# RF.net
KiCad netlist of a schematic drawn in Altium Designer
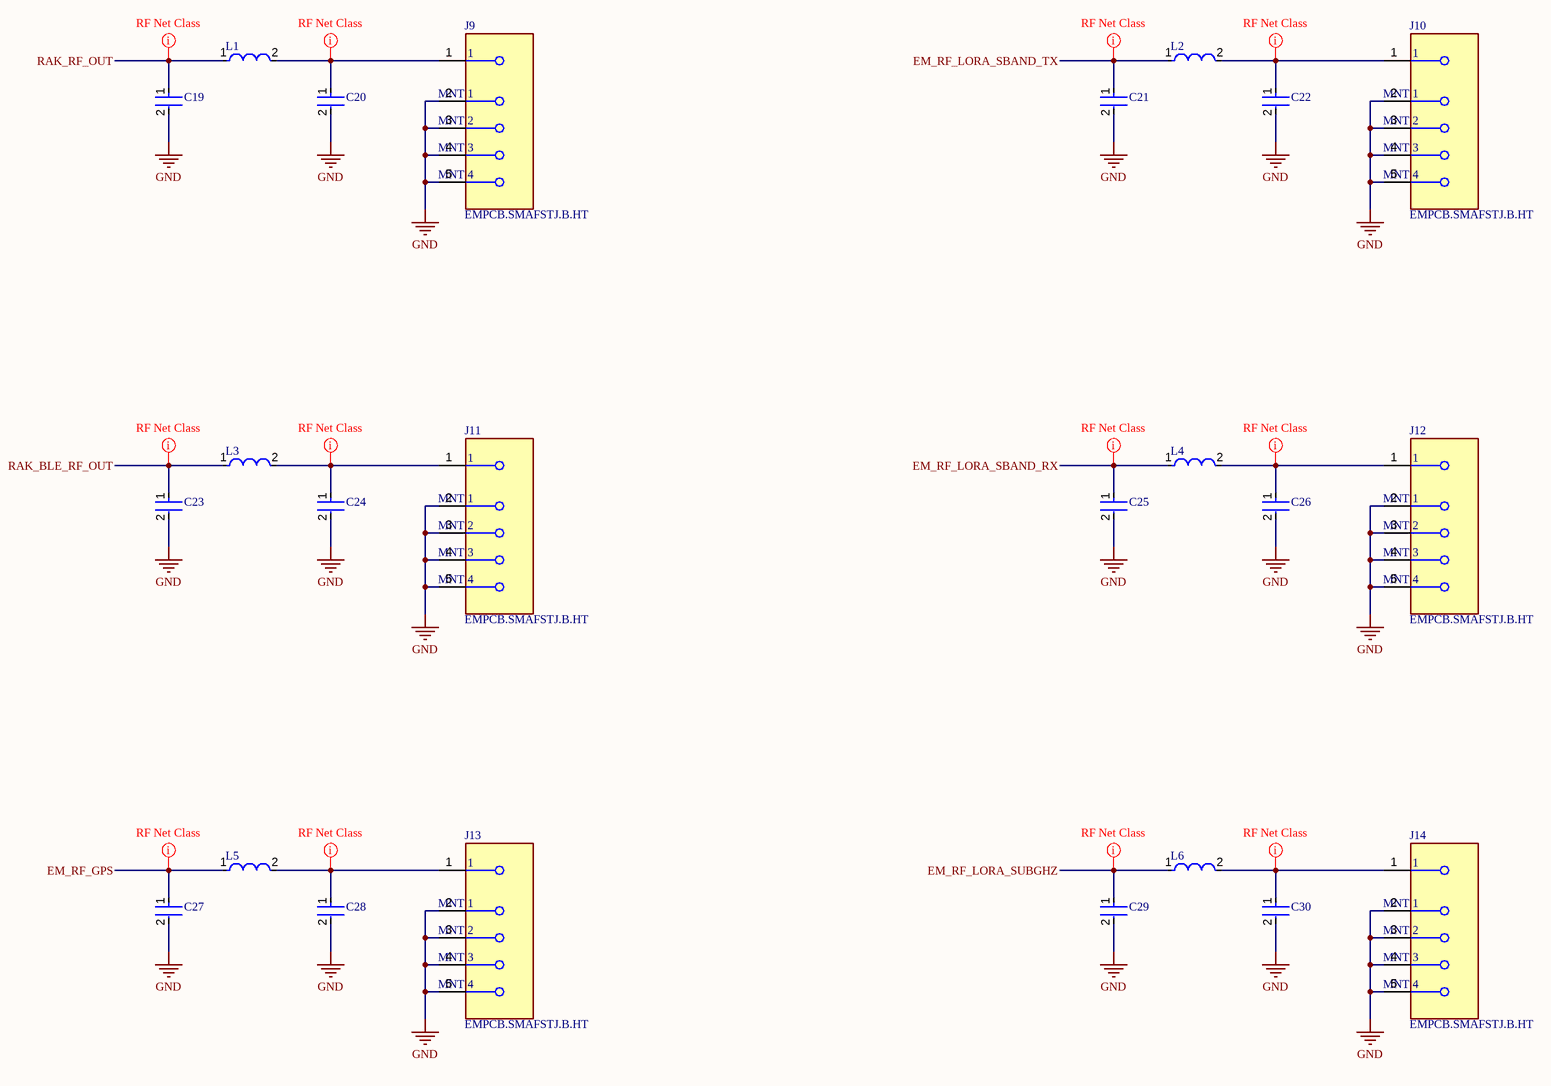
[diagram p0: RF.SchDoc]

(export (version "E")
  (design (tool "Eeschema 10.0.6"))
  (components
    (comp (ref "C19")
      (value "GJM1555C1H5R0CB01D")
      (footprint "FP-GJM155-0_05-MFG")
      (description "Multi-Layer Ceramic Capacitor 5pF C0G  ±0.25pF 0402 Paper T/R")
      (libsource (lib "ApolloEcho_Dev_Kit") (part "02cd4be3c70576c341d710602a673aa"))
    )
    (comp (ref "C20")
      (value "GJM1555C1H5R0CB01D")
      (footprint "FP-GJM155-0_05-MFG")
      (description "Multi-Layer Ceramic Capacitor 5pF C0G  ±0.25pF 0402 Paper T/R")
      (libsource (lib "ApolloEcho_Dev_Kit") (part "02cd4be3c70576c341d710602a673aa"))
    )
    (comp (ref "C21")
      (value "GJM1555C1H5R0CB01D")
      (footprint "FP-GJM155-0_05-MFG")
      (description "Multi-Layer Ceramic Capacitor 5pF C0G  ±0.25pF 0402 Paper T/R")
      (libsource (lib "ApolloEcho_Dev_Kit") (part "02cd4be3c70576c341d710602a673aa"))
    )
    (comp (ref "C22")
      (value "GJM1555C1H5R0CB01D")
      (footprint "FP-GJM155-0_05-MFG")
      (description "Multi-Layer Ceramic Capacitor 5pF C0G  ±0.25pF 0402 Paper T/R")
      (libsource (lib "ApolloEcho_Dev_Kit") (part "02cd4be3c70576c341d710602a673aa"))
    )
    (comp (ref "C23")
      (value "GJM1555C1H5R0CB01D")
      (footprint "FP-GJM155-0_05-MFG")
      (description "Multi-Layer Ceramic Capacitor 5pF C0G  ±0.25pF 0402 Paper T/R")
      (libsource (lib "ApolloEcho_Dev_Kit") (part "02cd4be3c70576c341d710602a673aa"))
    )
    (comp (ref "C24")
      (value "GJM1555C1H5R0CB01D")
      (footprint "FP-GJM155-0_05-MFG")
      (description "Multi-Layer Ceramic Capacitor 5pF C0G  ±0.25pF 0402 Paper T/R")
      (libsource (lib "ApolloEcho_Dev_Kit") (part "02cd4be3c70576c341d710602a673aa"))
    )
    (comp (ref "C25")
      (value "GJM1555C1H5R0CB01D")
      (footprint "FP-GJM155-0_05-MFG")
      (description "Multi-Layer Ceramic Capacitor 5pF C0G  ±0.25pF 0402 Paper T/R")
      (libsource (lib "ApolloEcho_Dev_Kit") (part "02cd4be3c70576c341d710602a673aa"))
    )
    (comp (ref "C26")
      (value "GJM1555C1H5R0CB01D")
      (footprint "FP-GJM155-0_05-MFG")
      (description "Multi-Layer Ceramic Capacitor 5pF C0G  ±0.25pF 0402 Paper T/R")
      (libsource (lib "ApolloEcho_Dev_Kit") (part "02cd4be3c70576c341d710602a673aa"))
    )
    (comp (ref "C27")
      (value "GJM1555C1H5R0CB01D")
      (footprint "FP-GJM155-0_05-MFG")
      (description "Multi-Layer Ceramic Capacitor 5pF C0G  ±0.25pF 0402 Paper T/R")
      (libsource (lib "ApolloEcho_Dev_Kit") (part "02cd4be3c70576c341d710602a673aa"))
    )
    (comp (ref "C28")
      (value "GJM1555C1H5R0CB01D")
      (footprint "FP-GJM155-0_05-MFG")
      (description "Multi-Layer Ceramic Capacitor 5pF C0G  ±0.25pF 0402 Paper T/R")
      (libsource (lib "ApolloEcho_Dev_Kit") (part "02cd4be3c70576c341d710602a673aa"))
    )
    (comp (ref "C29")
      (value "GJM1555C1H5R0CB01D")
      (footprint "FP-GJM155-0_05-MFG")
      (description "Multi-Layer Ceramic Capacitor 5pF C0G  ±0.25pF 0402 Paper T/R")
      (libsource (lib "ApolloEcho_Dev_Kit") (part "02cd4be3c70576c341d710602a673aa"))
    )
    (comp (ref "C30")
      (value "GJM1555C1H5R0CB01D")
      (footprint "FP-GJM155-0_05-MFG")
      (description "Multi-Layer Ceramic Capacitor 5pF C0G  ±0.25pF 0402 Paper T/R")
      (libsource (lib "ApolloEcho_Dev_Kit") (part "02cd4be3c70576c341d710602a673aa"))
    )
    (comp (ref "J9")
      (value "EMPCB.SMAFSTJ.B.HT")
      (footprint "FP-EMPCB_SMAFSTJ_B_HT-MFG")
      (description "CONN SMA JACK STR 50OHM EDGE MNT")
      (fields
        (field (name "OCTOPART") "https://octopart.com/empcb.smafstj.b.ht-taoglas-24204431")
        (field (name "MANUFACTURER") "Taoglas Limited")
      )
      (libsource (lib "ApolloEcho_Dev_Kit") (part "c65b8a639cdaef1819ea20b5466f8fa"))
    )
    (comp (ref "J10")
      (value "EMPCB.SMAFSTJ.B.HT")
      (footprint "FP-EMPCB_SMAFSTJ_B_HT-MFG")
      (description "CONN SMA JACK STR 50OHM EDGE MNT")
      (fields
        (field (name "OCTOPART") "https://octopart.com/empcb.smafstj.b.ht-taoglas-24204431")
        (field (name "MANUFACTURER") "Taoglas Limited")
      )
      (libsource (lib "ApolloEcho_Dev_Kit") (part "c65b8a639cdaef1819ea20b5466f8fa"))
    )
    (comp (ref "J11")
      (value "EMPCB.SMAFSTJ.B.HT")
      (footprint "FP-EMPCB_SMAFSTJ_B_HT-MFG")
      (description "CONN SMA JACK STR 50OHM EDGE MNT")
      (fields
        (field (name "OCTOPART") "https://octopart.com/empcb.smafstj.b.ht-taoglas-24204431")
        (field (name "MANUFACTURER") "Taoglas Limited")
      )
      (libsource (lib "ApolloEcho_Dev_Kit") (part "c65b8a639cdaef1819ea20b5466f8fa"))
    )
    (comp (ref "J12")
      (value "EMPCB.SMAFSTJ.B.HT")
      (footprint "FP-EMPCB_SMAFSTJ_B_HT-MFG")
      (description "CONN SMA JACK STR 50OHM EDGE MNT")
      (fields
        (field (name "OCTOPART") "https://octopart.com/empcb.smafstj.b.ht-taoglas-24204431")
        (field (name "MANUFACTURER") "Taoglas Limited")
      )
      (libsource (lib "ApolloEcho_Dev_Kit") (part "c65b8a639cdaef1819ea20b5466f8fa"))
    )
    (comp (ref "J13")
      (value "EMPCB.SMAFSTJ.B.HT")
      (footprint "FP-EMPCB_SMAFSTJ_B_HT-MFG")
      (description "CONN SMA JACK STR 50OHM EDGE MNT")
      (fields
        (field (name "OCTOPART") "https://octopart.com/empcb.smafstj.b.ht-taoglas-24204431")
        (field (name "MANUFACTURER") "Taoglas Limited")
      )
      (libsource (lib "ApolloEcho_Dev_Kit") (part "c65b8a639cdaef1819ea20b5466f8fa"))
    )
    (comp (ref "J14")
      (value "EMPCB.SMAFSTJ.B.HT")
      (footprint "FP-EMPCB_SMAFSTJ_B_HT-MFG")
      (description "CONN SMA JACK STR 50OHM EDGE MNT")
      (fields
        (field (name "OCTOPART") "https://octopart.com/empcb.smafstj.b.ht-taoglas-24204431")
        (field (name "MANUFACTURER") "Taoglas Limited")
      )
      (libsource (lib "ApolloEcho_Dev_Kit") (part "c65b8a639cdaef1819ea20b5466f8fa"))
    )
    (comp (ref "L1")
      (value "LQW15AN2N9D00D")
      (footprint "FP-LQW15AN_00-W0_6-0_1-MFG")
      (description "Wire Wound RF Inductor 2.9nH ±0.5nH 750mA 0.07Ω 0402 (1005)")
      (libsource (lib "ApolloEcho_Dev_Kit") (part "725321dda6339637d4d059423bc1c3c"))
    )
    (comp (ref "L2")
      (value "LQW15AN2N9D00D")
      (footprint "FP-LQW15AN_00-W0_6-0_1-MFG")
      (description "Wire Wound RF Inductor 2.9nH ±0.5nH 750mA 0.07Ω 0402 (1005)")
      (libsource (lib "ApolloEcho_Dev_Kit") (part "725321dda6339637d4d059423bc1c3c"))
    )
    (comp (ref "L3")
      (value "LQW15AN2N9D00D")
      (footprint "FP-LQW15AN_00-W0_6-0_1-MFG")
      (description "Wire Wound RF Inductor 2.9nH ±0.5nH 750mA 0.07Ω 0402 (1005)")
      (libsource (lib "ApolloEcho_Dev_Kit") (part "725321dda6339637d4d059423bc1c3c"))
    )
    (comp (ref "L4")
      (value "LQW15AN2N9D00D")
      (footprint "FP-LQW15AN_00-W0_6-0_1-MFG")
      (description "Wire Wound RF Inductor 2.9nH ±0.5nH 750mA 0.07Ω 0402 (1005)")
      (libsource (lib "ApolloEcho_Dev_Kit") (part "725321dda6339637d4d059423bc1c3c"))
    )
    (comp (ref "L5")
      (value "LQW15AN2N9D00D")
      (footprint "FP-LQW15AN_00-W0_6-0_1-MFG")
      (description "Wire Wound RF Inductor 2.9nH ±0.5nH 750mA 0.07Ω 0402 (1005)")
      (libsource (lib "ApolloEcho_Dev_Kit") (part "725321dda6339637d4d059423bc1c3c"))
    )
    (comp (ref "L6")
      (value "LQW15AN2N9D00D")
      (footprint "FP-LQW15AN_00-W0_6-0_1-MFG")
      (description "Wire Wound RF Inductor 2.9nH ±0.5nH 750mA 0.07Ω 0402 (1005)")
      (libsource (lib "ApolloEcho_Dev_Kit") (part "725321dda6339637d4d059423bc1c3c"))
    )
  )
  (nets
    (net (code "1") (name "/EM_RF_GPS") (class "Default")
      (node (ref "C27") (pin "1") (pinfunction "1_1") (pintype "passive"))
      (node (ref "L5") (pin "1") (pinfunction "1_1") (pintype "passive"))
    )
    (net (code "2") (name "/EM_RF_LORA_SBAND_RX") (class "Default")
      (node (ref "C25") (pin "1") (pinfunction "1_1") (pintype "passive"))
      (node (ref "L4") (pin "1") (pinfunction "1_1") (pintype "passive"))
    )
    (net (code "3") (name "/EM_RF_LORA_SBAND_TX") (class "Default")
      (node (ref "C21") (pin "1") (pinfunction "1_1") (pintype "passive"))
      (node (ref "L2") (pin "1") (pinfunction "1_1") (pintype "passive"))
    )
    (net (code "4") (name "/EM_RF_LORA_SUBGHZ") (class "Default")
      (node (ref "C29") (pin "1") (pinfunction "1_1") (pintype "passive"))
      (node (ref "L6") (pin "1") (pinfunction "1_1") (pintype "passive"))
    )
    (net (code "5") (name "/RAK_BLE_RF_OUT") (class "Default")
      (node (ref "C23") (pin "1") (pinfunction "1_1") (pintype "passive"))
      (node (ref "L3") (pin "1") (pinfunction "1_1") (pintype "passive"))
    )
    (net (code "6") (name "/RAK_RF_OUT") (class "Default")
      (node (ref "C19") (pin "1") (pinfunction "1_1") (pintype "passive"))
      (node (ref "L1") (pin "1") (pinfunction "1_1") (pintype "passive"))
    )
    (net (code "7") (name "GND") (class "Default")
      (node (ref "C19") (pin "2") (pinfunction "2_2") (pintype "passive"))
      (node (ref "C20") (pin "2") (pinfunction "2_2") (pintype "passive"))
      (node (ref "C21") (pin "2") (pinfunction "2_2") (pintype "passive"))
      (node (ref "C22") (pin "2") (pinfunction "2_2") (pintype "passive"))
      (node (ref "C23") (pin "2") (pinfunction "2_2") (pintype "passive"))
      (node (ref "C24") (pin "2") (pinfunction "2_2") (pintype "passive"))
      (node (ref "C25") (pin "2") (pinfunction "2_2") (pintype "passive"))
      (node (ref "C26") (pin "2") (pinfunction "2_2") (pintype "passive"))
      (node (ref "C27") (pin "2") (pinfunction "2_2") (pintype "passive"))
      (node (ref "C28") (pin "2") (pinfunction "2_2") (pintype "passive"))
      (node (ref "C29") (pin "2") (pinfunction "2_2") (pintype "passive"))
      (node (ref "C30") (pin "2") (pinfunction "2_2") (pintype "passive"))
      (node (ref "J10") (pin "2") (pinfunction "MNT_1_2") (pintype "passive"))
      (node (ref "J10") (pin "3") (pinfunction "MNT_2_3") (pintype "passive"))
      (node (ref "J10") (pin "4") (pinfunction "MNT_3_4") (pintype "passive"))
      (node (ref "J10") (pin "5") (pinfunction "MNT_4_5") (pintype "passive"))
      (node (ref "J11") (pin "2") (pinfunction "MNT_1_2") (pintype "passive"))
      (node (ref "J11") (pin "3") (pinfunction "MNT_2_3") (pintype "passive"))
      (node (ref "J11") (pin "4") (pinfunction "MNT_3_4") (pintype "passive"))
      (node (ref "J11") (pin "5") (pinfunction "MNT_4_5") (pintype "passive"))
      (node (ref "J12") (pin "2") (pinfunction "MNT_1_2") (pintype "passive"))
      (node (ref "J12") (pin "3") (pinfunction "MNT_2_3") (pintype "passive"))
      (node (ref "J12") (pin "4") (pinfunction "MNT_3_4") (pintype "passive"))
      (node (ref "J12") (pin "5") (pinfunction "MNT_4_5") (pintype "passive"))
      (node (ref "J13") (pin "2") (pinfunction "MNT_1_2") (pintype "passive"))
      (node (ref "J13") (pin "3") (pinfunction "MNT_2_3") (pintype "passive"))
      (node (ref "J13") (pin "4") (pinfunction "MNT_3_4") (pintype "passive"))
      (node (ref "J13") (pin "5") (pinfunction "MNT_4_5") (pintype "passive"))
      (node (ref "J14") (pin "2") (pinfunction "MNT_1_2") (pintype "passive"))
      (node (ref "J14") (pin "3") (pinfunction "MNT_2_3") (pintype "passive"))
      (node (ref "J14") (pin "4") (pinfunction "MNT_3_4") (pintype "passive"))
      (node (ref "J14") (pin "5") (pinfunction "MNT_4_5") (pintype "passive"))
      (node (ref "J9") (pin "2") (pinfunction "MNT_1_2") (pintype "passive"))
      (node (ref "J9") (pin "3") (pinfunction "MNT_2_3") (pintype "passive"))
      (node (ref "J9") (pin "4") (pinfunction "MNT_3_4") (pintype "passive"))
      (node (ref "J9") (pin "5") (pinfunction "MNT_4_5") (pintype "passive"))
    )
    (net (code "8") (name "Net-(C20-Pad1)") (class "Default")
      (node (ref "C20") (pin "1") (pinfunction "1_1") (pintype "passive"))
      (node (ref "J9") (pin "1") (pinfunction "1_1") (pintype "passive"))
      (node (ref "L1") (pin "2") (pinfunction "2_2") (pintype "passive"))
    )
    (net (code "9") (name "Net-(C22-Pad1)") (class "Default")
      (node (ref "C22") (pin "1") (pinfunction "1_1") (pintype "passive"))
      (node (ref "J10") (pin "1") (pinfunction "1_1") (pintype "passive"))
      (node (ref "L2") (pin "2") (pinfunction "2_2") (pintype "passive"))
    )
    (net (code "10") (name "Net-(C24-Pad1)") (class "Default")
      (node (ref "C24") (pin "1") (pinfunction "1_1") (pintype "passive"))
      (node (ref "J11") (pin "1") (pinfunction "1_1") (pintype "passive"))
      (node (ref "L3") (pin "2") (pinfunction "2_2") (pintype "passive"))
    )
    (net (code "11") (name "Net-(C26-Pad1)") (class "Default")
      (node (ref "C26") (pin "1") (pinfunction "1_1") (pintype "passive"))
      (node (ref "J12") (pin "1") (pinfunction "1_1") (pintype "passive"))
      (node (ref "L4") (pin "2") (pinfunction "2_2") (pintype "passive"))
    )
    (net (code "12") (name "Net-(C28-Pad1)") (class "Default")
      (node (ref "C28") (pin "1") (pinfunction "1_1") (pintype "passive"))
      (node (ref "J13") (pin "1") (pinfunction "1_1") (pintype "passive"))
      (node (ref "L5") (pin "2") (pinfunction "2_2") (pintype "passive"))
    )
    (net (code "13") (name "Net-(C30-Pad1)") (class "Default")
      (node (ref "C30") (pin "1") (pinfunction "1_1") (pintype "passive"))
      (node (ref "J14") (pin "1") (pinfunction "1_1") (pintype "passive"))
      (node (ref "L6") (pin "2") (pinfunction "2_2") (pintype "passive"))
    )
  )
)
